# LCD_sterowanie.net
KiCad netlist of a schematic drawn in EAGLE
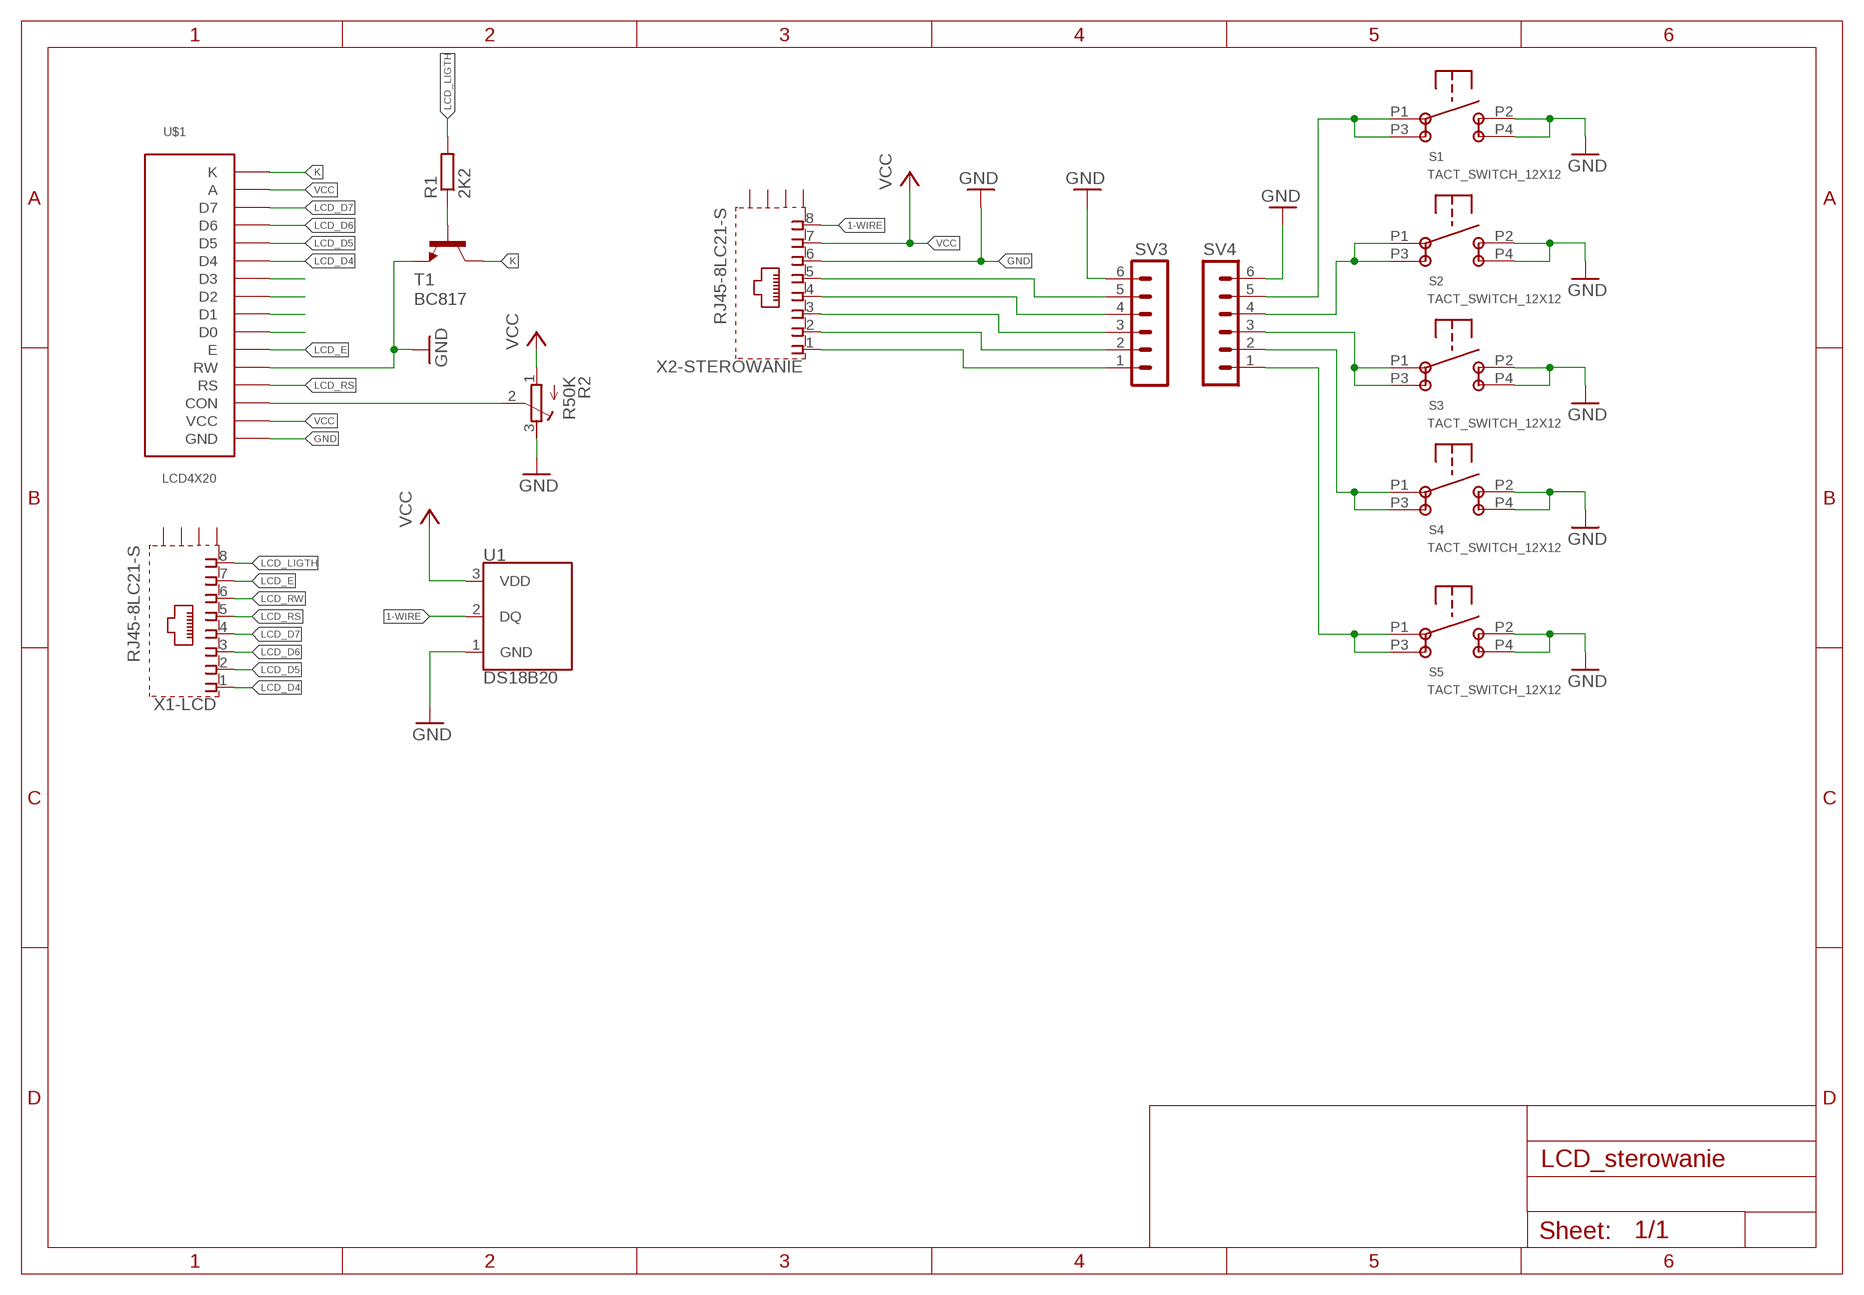
[diagram p0: schematic, sheet 1]

(export (version "E")
  (design (tool "Eeschema 10.0.6"))
  (components
    (comp (ref "R1")
      (value "2K2")
      (footprint "eagle-import:M0805")
      (libsource (lib "eagle-import") (part "R-EU_M0805"))
    )
    (comp (ref "R2")
      (value "R50K")
      (footprint "eagle-import:RTRIM3296P")
      (libsource (lib "eagle-import") (part "R-TRIMM3296P"))
    )
    (comp (ref "S1")
      (value "TACT_SWITCH_12X12")
      (footprint "eagle-import:TACT_SWITCH_12X12")
      (libsource (lib "eagle-import") (part "TACT_SWITCH_12X12"))
    )
    (comp (ref "S2")
      (value "TACT_SWITCH_12X12")
      (footprint "eagle-import:TACT_SWITCH_12X12")
      (libsource (lib "eagle-import") (part "TACT_SWITCH_12X12"))
    )
    (comp (ref "S3")
      (value "TACT_SWITCH_12X12")
      (footprint "eagle-import:TACT_SWITCH_12X12")
      (libsource (lib "eagle-import") (part "TACT_SWITCH_12X12"))
    )
    (comp (ref "S4")
      (value "TACT_SWITCH_12X12")
      (footprint "eagle-import:TACT_SWITCH_12X12")
      (libsource (lib "eagle-import") (part "TACT_SWITCH_12X12"))
    )
    (comp (ref "S5")
      (value "TACT_SWITCH_12X12")
      (footprint "eagle-import:TACT_SWITCH_12X12")
      (libsource (lib "eagle-import") (part "TACT_SWITCH_12X12"))
    )
    (comp (ref "SV3")
      (value "MA06-1")
      (footprint "eagle-import:MA06-1")
      (libsource (lib "eagle-import") (part "MA06-1"))
    )
    (comp (ref "SV4")
      (value "MA06-1")
      (footprint "eagle-import:MA06-1")
      (libsource (lib "eagle-import") (part "MA06-1"))
    )
    (comp (ref "T1")
      (value "BC817")
      (footprint "eagle-import:SOT23")
      (libsource (lib "eagle-import") (part "BC847"))
    )
    (comp (ref "U$1")
      (value "LCD4X20")
      (footprint "eagle-import:LCD4X20")
      (libsource (lib "eagle-import") (part "LCD4X20"))
    )
    (comp (ref "U1")
      (value "DS18B20")
      (footprint "eagle-import:TO-92-AMMO")
      (libsource (lib "eagle-import") (part "DS18B20"))
    )
    (comp (ref "X1-LCD")
      (value "RJ45-8LC21-S")
      (footprint "eagle-import:RJ45-SHIELD1")
      (libsource (lib "eagle-import") (part "RJ4521-S-8LC"))
    )
    (comp (ref "X2-STEROWANIE")
      (value "RJ45-8LC21-S")
      (footprint "eagle-import:RJ45-SHIELD1")
      (libsource (lib "eagle-import") (part "RJ4521-S-8LC"))
    )
  )
  (nets
    (net (code "1") (name "1-WIRE") (class "Default")
      (node (ref "U1") (pin "2") (pinfunction "DQ_2") (pintype "bidirectional"))
      (node (ref "X2-STEROWANIE") (pin "8") (pinfunction "8_8") (pintype "passive"))
    )
    (net (code "2") (name "GND") (class "Default")
      (node (ref "R2") (pin "3") (pinfunction "E_3") (pintype "passive"))
      (node (ref "S1") (pin "P2") (pinfunction "P$2_P2") (pintype "bidirectional"))
      (node (ref "S1") (pin "P4") (pinfunction "P$4_P4") (pintype "bidirectional"))
      (node (ref "S2") (pin "P2") (pinfunction "P$2_P2") (pintype "bidirectional"))
      (node (ref "S2") (pin "P4") (pinfunction "P$4_P4") (pintype "bidirectional"))
      (node (ref "S3") (pin "P2") (pinfunction "P$2_P2") (pintype "bidirectional"))
      (node (ref "S3") (pin "P4") (pinfunction "P$4_P4") (pintype "bidirectional"))
      (node (ref "S4") (pin "P2") (pinfunction "P$2_P2") (pintype "bidirectional"))
      (node (ref "S4") (pin "P4") (pinfunction "P$4_P4") (pintype "bidirectional"))
      (node (ref "S5") (pin "P2") (pinfunction "P$2_P2") (pintype "bidirectional"))
      (node (ref "S5") (pin "P4") (pinfunction "P$4_P4") (pintype "bidirectional"))
      (node (ref "SV3") (pin "6") (pinfunction "6_6") (pintype "passive"))
      (node (ref "SV4") (pin "6") (pinfunction "6_6") (pintype "passive"))
      (node (ref "T1") (pin "2") (pinfunction "E_2") (pintype "passive"))
      (node (ref "U$1") (pin "GND") (pinfunction "GND_GND") (pintype "bidirectional"))
      (node (ref "U$1") (pin "RW") (pinfunction "RW_RW") (pintype "bidirectional"))
      (node (ref "U1") (pin "1") (pinfunction "GND_1") (pintype "power_in"))
      (node (ref "X2-STEROWANIE") (pin "6") (pinfunction "6_6") (pintype "passive"))
    )
    (net (code "3") (name "K") (class "Default")
      (node (ref "T1") (pin "3") (pinfunction "C_3") (pintype "passive"))
      (node (ref "U$1") (pin "K") (pinfunction "K_K") (pintype "bidirectional"))
    )
    (net (code "4") (name "LCD_D4") (class "Default")
      (node (ref "U$1") (pin "D4") (pinfunction "D4_D4") (pintype "bidirectional"))
      (node (ref "X1-LCD") (pin "1") (pinfunction "1_1") (pintype "passive"))
    )
    (net (code "5") (name "LCD_D5") (class "Default")
      (node (ref "U$1") (pin "D5") (pinfunction "D5_D5") (pintype "bidirectional"))
      (node (ref "X1-LCD") (pin "2") (pinfunction "2_2") (pintype "passive"))
    )
    (net (code "6") (name "LCD_D6") (class "Default")
      (node (ref "U$1") (pin "D6") (pinfunction "D6_D6") (pintype "bidirectional"))
      (node (ref "X1-LCD") (pin "3") (pinfunction "3_3") (pintype "passive"))
    )
    (net (code "7") (name "LCD_D7") (class "Default")
      (node (ref "U$1") (pin "D7") (pinfunction "D7_D7") (pintype "bidirectional"))
      (node (ref "X1-LCD") (pin "4") (pinfunction "4_4") (pintype "passive"))
    )
    (net (code "8") (name "LCD_E") (class "Default")
      (node (ref "U$1") (pin "E") (pinfunction "E_E") (pintype "bidirectional"))
      (node (ref "X1-LCD") (pin "7") (pinfunction "7_7") (pintype "passive"))
    )
    (net (code "9") (name "LCD_LIGTH") (class "Default")
      (node (ref "R1") (pin "2") (pinfunction "2_2") (pintype "passive"))
      (node (ref "X1-LCD") (pin "8") (pinfunction "8_8") (pintype "passive"))
    )
    (net (code "10") (name "LCD_RS") (class "Default")
      (node (ref "U$1") (pin "RS") (pinfunction "RS_RS") (pintype "bidirectional"))
      (node (ref "X1-LCD") (pin "5") (pinfunction "5_5") (pintype "passive"))
    )
    (net (code "11") (name "LCD_RW") (class "Default")
      (node (ref "X1-LCD") (pin "6") (pinfunction "6_6") (pintype "passive"))
    )
    (net (code "12") (name "Net-(R2-S)") (class "Default")
      (node (ref "R2") (pin "2") (pinfunction "S_2") (pintype "passive"))
      (node (ref "U$1") (pin "CON") (pinfunction "CON_CON") (pintype "bidirectional"))
    )
    (net (code "13") (name "Net-(S1-P$1)") (class "Default")
      (node (ref "S1") (pin "P1") (pinfunction "P$1_P1") (pintype "bidirectional"))
      (node (ref "S1") (pin "P3") (pinfunction "P$3_P3") (pintype "bidirectional"))
      (node (ref "SV4") (pin "5") (pinfunction "5_5") (pintype "passive"))
    )
    (net (code "14") (name "Net-(S2-P$1)") (class "Default")
      (node (ref "S2") (pin "P1") (pinfunction "P$1_P1") (pintype "bidirectional"))
      (node (ref "S2") (pin "P3") (pinfunction "P$3_P3") (pintype "bidirectional"))
      (node (ref "SV4") (pin "4") (pinfunction "4_4") (pintype "passive"))
    )
    (net (code "15") (name "Net-(S3-P$1)") (class "Default")
      (node (ref "S3") (pin "P1") (pinfunction "P$1_P1") (pintype "bidirectional"))
      (node (ref "S3") (pin "P3") (pinfunction "P$3_P3") (pintype "bidirectional"))
      (node (ref "SV4") (pin "3") (pinfunction "3_3") (pintype "passive"))
    )
    (net (code "16") (name "Net-(S4-P$1)") (class "Default")
      (node (ref "S4") (pin "P1") (pinfunction "P$1_P1") (pintype "bidirectional"))
      (node (ref "S4") (pin "P3") (pinfunction "P$3_P3") (pintype "bidirectional"))
      (node (ref "SV4") (pin "2") (pinfunction "2_2") (pintype "passive"))
    )
    (net (code "17") (name "Net-(S5-P$1)") (class "Default")
      (node (ref "S5") (pin "P1") (pinfunction "P$1_P1") (pintype "bidirectional"))
      (node (ref "S5") (pin "P3") (pinfunction "P$3_P3") (pintype "bidirectional"))
      (node (ref "SV4") (pin "1") (pinfunction "1_1") (pintype "passive"))
    )
    (net (code "18") (name "Net-(SV3-Pad1)") (class "Default")
      (node (ref "SV3") (pin "1") (pinfunction "1_1") (pintype "passive"))
      (node (ref "X2-STEROWANIE") (pin "1") (pinfunction "1_1") (pintype "passive"))
    )
    (net (code "19") (name "Net-(SV3-Pad2)") (class "Default")
      (node (ref "SV3") (pin "2") (pinfunction "2_2") (pintype "passive"))
      (node (ref "X2-STEROWANIE") (pin "2") (pinfunction "2_2") (pintype "passive"))
    )
    (net (code "20") (name "Net-(SV3-Pad3)") (class "Default")
      (node (ref "SV3") (pin "3") (pinfunction "3_3") (pintype "passive"))
      (node (ref "X2-STEROWANIE") (pin "3") (pinfunction "3_3") (pintype "passive"))
    )
    (net (code "21") (name "Net-(SV3-Pad4)") (class "Default")
      (node (ref "SV3") (pin "4") (pinfunction "4_4") (pintype "passive"))
      (node (ref "X2-STEROWANIE") (pin "4") (pinfunction "4_4") (pintype "passive"))
    )
    (net (code "22") (name "Net-(SV3-Pad5)") (class "Default")
      (node (ref "SV3") (pin "5") (pinfunction "5_5") (pintype "passive"))
      (node (ref "X2-STEROWANIE") (pin "5") (pinfunction "5_5") (pintype "passive"))
    )
    (net (code "23") (name "Net-(T1-B)") (class "Default")
      (node (ref "R1") (pin "1") (pinfunction "1_1") (pintype "passive"))
      (node (ref "T1") (pin "1") (pinfunction "B_1") (pintype "passive"))
    )
    (net (code "24") (name "VCC") (class "Default")
      (node (ref "R2") (pin "1") (pinfunction "A_1") (pintype "passive"))
      (node (ref "U$1") (pin "A") (pinfunction "A_A") (pintype "bidirectional"))
      (node (ref "U$1") (pin "VCC") (pinfunction "VCC_VCC") (pintype "bidirectional"))
      (node (ref "U1") (pin "3") (pinfunction "VDD_3") (pintype "power_in"))
      (node (ref "X2-STEROWANIE") (pin "7") (pinfunction "7_7") (pintype "passive"))
    )
    (net (code "25") (name "unconnected-(U$1-PadD0)") (class "Default")
      (node (ref "U$1") (pin "D0") (pinfunction "D0_D0") (pintype "bidirectional"))
    )
    (net (code "26") (name "unconnected-(U$1-PadD1)") (class "Default")
      (node (ref "U$1") (pin "D1") (pinfunction "D1_D1") (pintype "bidirectional"))
    )
    (net (code "27") (name "unconnected-(U$1-PadD2)") (class "Default")
      (node (ref "U$1") (pin "D2") (pinfunction "D2_D2") (pintype "bidirectional"))
    )
    (net (code "28") (name "unconnected-(U$1-PadD3)") (class "Default")
      (node (ref "U$1") (pin "D3") (pinfunction "D3_D3") (pintype "bidirectional"))
    )
    (net (code "29") (name "unconnected-(X1-LCD-S-PadS1)") (class "Default")
      (node (ref "X1-LCD") (pin "S1") (pinfunction "S_S1") (pintype "passive"))
    )
    (net (code "30") (name "unconnected-(X1-LCD-S-PadS2)") (class "Default")
      (node (ref "X1-LCD") (pin "S2") (pinfunction "S_S2") (pintype "passive"))
    )
    (net (code "31") (name "unconnected-(X1-LCD-S-PadS3)") (class "Default")
      (node (ref "X1-LCD") (pin "S3") (pinfunction "S_S3") (pintype "passive"))
    )
    (net (code "32") (name "unconnected-(X1-LCD-S-PadS4)") (class "Default")
      (node (ref "X1-LCD") (pin "S4") (pinfunction "S_S4") (pintype "passive"))
    )
    (net (code "33") (name "unconnected-(X2-STEROWANIE-S-PadS1)") (class "Default")
      (node (ref "X2-STEROWANIE") (pin "S1") (pinfunction "S_S1") (pintype "passive"))
    )
    (net (code "34") (name "unconnected-(X2-STEROWANIE-S-PadS2)") (class "Default")
      (node (ref "X2-STEROWANIE") (pin "S2") (pinfunction "S_S2") (pintype "passive"))
    )
    (net (code "35") (name "unconnected-(X2-STEROWANIE-S-PadS3)") (class "Default")
      (node (ref "X2-STEROWANIE") (pin "S3") (pinfunction "S_S3") (pintype "passive"))
    )
    (net (code "36") (name "unconnected-(X2-STEROWANIE-S-PadS4)") (class "Default")
      (node (ref "X2-STEROWANIE") (pin "S4") (pinfunction "S_S4") (pintype "passive"))
    )
  )
)
